# MINIL.net
KiCad netlist of a schematic drawn in EAGLE
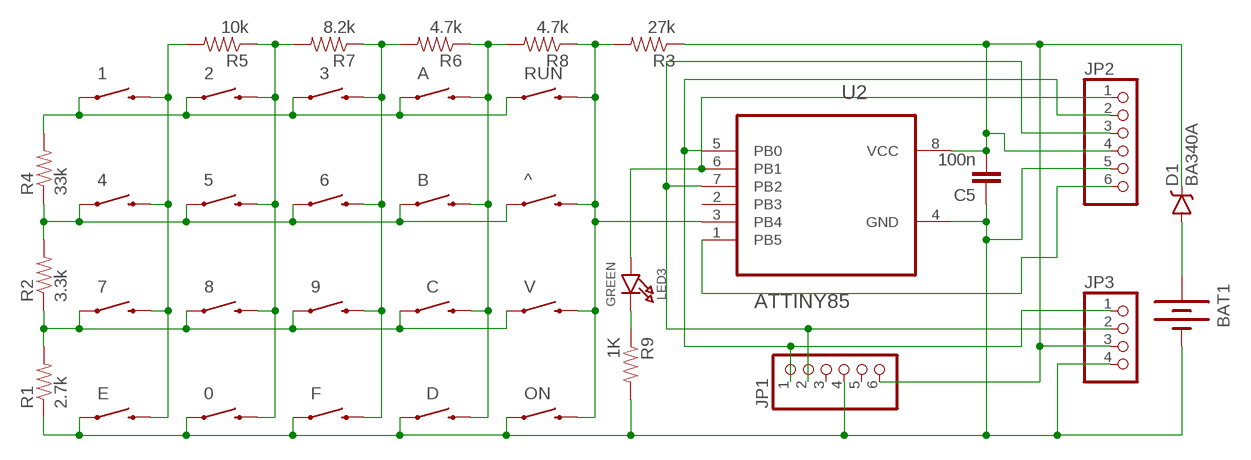
[diagram p0: schematic, sheet 1]

(export (version "E")
  (design (tool "Eeschema 10.0.6"))
  (components
    (comp (ref "0")
      (value "SWITCH-MOMENTARY-2PTH")
      (footprint "eagle-import:TACTILE-PTH")
      (libsource (lib "eagle-import") (part "SWITCH-MOMENTARY-2PTH"))
    )
    (comp (ref "1")
      (value "SWITCH-MOMENTARY-2PTH")
      (footprint "eagle-import:TACTILE-PTH")
      (libsource (lib "eagle-import") (part "SWITCH-MOMENTARY-2PTH"))
    )
    (comp (ref "2")
      (value "SWITCH-MOMENTARY-2PTH")
      (footprint "eagle-import:TACTILE-PTH")
      (libsource (lib "eagle-import") (part "SWITCH-MOMENTARY-2PTH"))
    )
    (comp (ref "3")
      (value "SWITCH-MOMENTARY-2PTH")
      (footprint "eagle-import:TACTILE-PTH")
      (libsource (lib "eagle-import") (part "SWITCH-MOMENTARY-2PTH"))
    )
    (comp (ref "4")
      (value "SWITCH-MOMENTARY-2PTH")
      (footprint "eagle-import:TACTILE-PTH")
      (libsource (lib "eagle-import") (part "SWITCH-MOMENTARY-2PTH"))
    )
    (comp (ref "5")
      (value "SWITCH-MOMENTARY-2PTH")
      (footprint "eagle-import:TACTILE-PTH")
      (libsource (lib "eagle-import") (part "SWITCH-MOMENTARY-2PTH"))
    )
    (comp (ref "6")
      (value "SWITCH-MOMENTARY-2PTH")
      (footprint "eagle-import:TACTILE-PTH")
      (libsource (lib "eagle-import") (part "SWITCH-MOMENTARY-2PTH"))
    )
    (comp (ref "7")
      (value "SWITCH-MOMENTARY-2PTH")
      (footprint "eagle-import:TACTILE-PTH")
      (libsource (lib "eagle-import") (part "SWITCH-MOMENTARY-2PTH"))
    )
    (comp (ref "8")
      (value "SWITCH-MOMENTARY-2PTH")
      (footprint "eagle-import:TACTILE-PTH")
      (libsource (lib "eagle-import") (part "SWITCH-MOMENTARY-2PTH"))
    )
    (comp (ref "9")
      (value "SWITCH-MOMENTARY-2PTH")
      (footprint "eagle-import:TACTILE-PTH")
      (libsource (lib "eagle-import") (part "SWITCH-MOMENTARY-2PTH"))
    )
    (comp (ref "A")
      (value "SWITCH-MOMENTARY-2PTH")
      (footprint "eagle-import:TACTILE-PTH")
      (libsource (lib "eagle-import") (part "SWITCH-MOMENTARY-2PTH"))
    )
    (comp (ref "B")
      (value "SWITCH-MOMENTARY-2PTH")
      (footprint "eagle-import:TACTILE-PTH")
      (libsource (lib "eagle-import") (part "SWITCH-MOMENTARY-2PTH"))
    )
    (comp (ref "BAT1")
      (value "BATTERYAAA-KIT")
      (footprint "eagle-import:BATTERY-AAA-KIT")
      (libsource (lib "eagle-import") (part "BATTERYAAA-KIT"))
    )
    (comp (ref "C")
      (value "SWITCH-MOMENTARY-2PTH")
      (footprint "eagle-import:TACTILE-PTH")
      (libsource (lib "eagle-import") (part "SWITCH-MOMENTARY-2PTH"))
    )
    (comp (ref "C5")
      (value "100n")
      (footprint "eagle-import:0603-CAP")
      (libsource (lib "eagle-import") (part "CAP0603-CAP"))
    )
    (comp (ref "D")
      (value "SWITCH-MOMENTARY-2PTH")
      (footprint "eagle-import:TACTILE-PTH")
      (libsource (lib "eagle-import") (part "SWITCH-MOMENTARY-2PTH"))
    )
    (comp (ref "D1")
      (value "BA340A")
      (footprint "eagle-import:SMA-DIODE")
      (libsource (lib "eagle-import") (part "B340A"))
    )
    (comp (ref "E")
      (value "SWITCH-MOMENTARY-2PTH")
      (footprint "eagle-import:TACTILE-PTH")
      (libsource (lib "eagle-import") (part "SWITCH-MOMENTARY-2PTH"))
    )
    (comp (ref "F")
      (value "SWITCH-MOMENTARY-2PTH")
      (footprint "eagle-import:TACTILE-PTH")
      (libsource (lib "eagle-import") (part "SWITCH-MOMENTARY-2PTH"))
    )
    (comp (ref "JP1")
      (value "HEADER-1X6ROUND")
      (footprint "eagle-import:1X06_ROUND")
      (libsource (lib "eagle-import") (part "HEADER-1X6ROUND"))
    )
    (comp (ref "JP2")
      (value "PINHD-1X6CLEAN")
      (footprint "eagle-import:1X06-CLEAN")
      (libsource (lib "eagle-import") (part "PINHD-1X6CLEAN"))
    )
    (comp (ref "JP3")
      (value "HEADER-1X4ROUND")
      (footprint "eagle-import:1X04_ROUND")
      (libsource (lib "eagle-import") (part "HEADER-1X4ROUND"))
    )
    (comp (ref "LED3")
      (value "GREEN")
      (footprint "eagle-import:CHIPLED_0805_NOOUTLINE")
      (libsource (lib "eagle-import") (part "LED0805_NOOUTLINE"))
    )
    (comp (ref "ON")
      (value "SWITCH-MOMENTARY-2PTH")
      (footprint "eagle-import:TACTILE-PTH")
      (libsource (lib "eagle-import") (part "SWITCH-MOMENTARY-2PTH"))
    )
    (comp (ref "R1")
      (value "2.7k")
      (footprint "eagle-import:0805")
      (libsource (lib "eagle-import") (part "0.3OHM-1/8W-1%(0805)"))
    )
    (comp (ref "R2")
      (value "3.3k")
      (footprint "eagle-import:0805")
      (libsource (lib "eagle-import") (part "0.3OHM-1/8W-1%(0805)"))
    )
    (comp (ref "R3")
      (value "27k")
      (footprint "eagle-import:0805")
      (libsource (lib "eagle-import") (part "0.3OHM-1/8W-1%(0805)"))
    )
    (comp (ref "R4")
      (value "33k")
      (footprint "eagle-import:0805")
      (libsource (lib "eagle-import") (part "0.3OHM-1/8W-1%(0805)"))
    )
    (comp (ref "R5")
      (value "10k")
      (footprint "eagle-import:0805")
      (libsource (lib "eagle-import") (part "0.3OHM-1/8W-1%(0805)"))
    )
    (comp (ref "R6")
      (value "4.7k")
      (footprint "eagle-import:0805")
      (libsource (lib "eagle-import") (part "0.3OHM-1/8W-1%(0805)"))
    )
    (comp (ref "R7")
      (value "8.2k")
      (footprint "eagle-import:0805")
      (libsource (lib "eagle-import") (part "0.3OHM-1/8W-1%(0805)"))
    )
    (comp (ref "R8")
      (value "4.7k")
      (footprint "eagle-import:0805")
      (libsource (lib "eagle-import") (part "0.3OHM-1/8W-1%(0805)"))
    )
    (comp (ref "R9")
      (value "1K")
      (footprint "eagle-import:0805")
      (libsource (lib "eagle-import") (part "0.3OHM-1/8W-1%(0805)"))
    )
    (comp (ref "RUN")
      (value "SWITCH-MOMENTARY-2PTH")
      (footprint "eagle-import:TACTILE-PTH")
      (libsource (lib "eagle-import") (part "SWITCH-MOMENTARY-2PTH"))
    )
    (comp (ref "U2")
      (value "ATTINY85")
      (footprint "eagle-import:SOIC127P798X216-8N")
      (fields (field (name "MPN") "ATTINY85-20SU"))
      (libsource (lib "eagle-import") (part "ATTINY85-20SU"))
    )
    (comp (ref "V")
      (value "SWITCH-MOMENTARY-2PTH")
      (footprint "eagle-import:TACTILE-PTH")
      (libsource (lib "eagle-import") (part "SWITCH-MOMENTARY-2PTH"))
    )
    (comp (ref "^")
      (value "SWITCH-MOMENTARY-2PTH")
      (footprint "eagle-import:TACTILE-PTH")
      (libsource (lib "eagle-import") (part "SWITCH-MOMENTARY-2PTH"))
    )
  )
  (nets
    (net (code "1") (name "Net-(0-2)") (class "Default")
      (node (ref "0") (pin "3") (pinfunction "2_3") (pintype "passive"))
      (node (ref "2") (pin "3") (pinfunction "2_3") (pintype "passive"))
      (node (ref "5") (pin "3") (pinfunction "2_3") (pintype "passive"))
      (node (ref "8") (pin "3") (pinfunction "2_3") (pintype "passive"))
      (node (ref "R5") (pin "1") (pinfunction "1_1") (pintype "passive"))
      (node (ref "R7") (pin "2") (pinfunction "2_2") (pintype "passive"))
    )
    (net (code "2") (name "Net-(1-2)") (class "Default")
      (node (ref "1") (pin "3") (pinfunction "2_3") (pintype "passive"))
      (node (ref "4") (pin "3") (pinfunction "2_3") (pintype "passive"))
      (node (ref "7") (pin "3") (pinfunction "2_3") (pintype "passive"))
      (node (ref "E") (pin "3") (pinfunction "2_3") (pintype "passive"))
      (node (ref "R5") (pin "2") (pinfunction "2_2") (pintype "passive"))
    )
    (net (code "3") (name "Net-(1-Pad1)") (class "Default")
      (node (ref "1") (pin "1") (pinfunction "1_1") (pintype "passive"))
      (node (ref "2") (pin "1") (pinfunction "1_1") (pintype "passive"))
      (node (ref "3") (pin "1") (pinfunction "1_1") (pintype "passive"))
      (node (ref "A") (pin "1") (pinfunction "1_1") (pintype "passive"))
      (node (ref "R4") (pin "2") (pinfunction "2_2") (pintype "passive"))
      (node (ref "RUN") (pin "1") (pinfunction "1_1") (pintype "passive"))
    )
    (net (code "4") (name "Net-(3-2)") (class "Default")
      (node (ref "3") (pin "3") (pinfunction "2_3") (pintype "passive"))
      (node (ref "6") (pin "3") (pinfunction "2_3") (pintype "passive"))
      (node (ref "9") (pin "3") (pinfunction "2_3") (pintype "passive"))
      (node (ref "F") (pin "3") (pinfunction "2_3") (pintype "passive"))
      (node (ref "R6") (pin "2") (pinfunction "2_2") (pintype "passive"))
      (node (ref "R7") (pin "1") (pinfunction "1_1") (pintype "passive"))
    )
    (net (code "5") (name "Net-(4-Pad1)") (class "Default")
      (node (ref "4") (pin "1") (pinfunction "1_1") (pintype "passive"))
      (node (ref "5") (pin "1") (pinfunction "1_1") (pintype "passive"))
      (node (ref "6") (pin "1") (pinfunction "1_1") (pintype "passive"))
      (node (ref "B") (pin "1") (pinfunction "1_1") (pintype "passive"))
      (node (ref "R2") (pin "2") (pinfunction "2_2") (pintype "passive"))
      (node (ref "R4") (pin "1") (pinfunction "1_1") (pintype "passive"))
      (node (ref "^") (pin "1") (pinfunction "1_1") (pintype "passive"))
    )
    (net (code "6") (name "Net-(7-Pad1)") (class "Default")
      (node (ref "7") (pin "1") (pinfunction "1_1") (pintype "passive"))
      (node (ref "8") (pin "1") (pinfunction "1_1") (pintype "passive"))
      (node (ref "9") (pin "1") (pinfunction "1_1") (pintype "passive"))
      (node (ref "C") (pin "1") (pinfunction "1_1") (pintype "passive"))
      (node (ref "R1") (pin "2") (pinfunction "2_2") (pintype "passive"))
      (node (ref "R2") (pin "1") (pinfunction "1_1") (pintype "passive"))
      (node (ref "V") (pin "1") (pinfunction "1_1") (pintype "passive"))
    )
    (net (code "7") (name "Net-(A-2)") (class "Default")
      (node (ref "A") (pin "3") (pinfunction "2_3") (pintype "passive"))
      (node (ref "B") (pin "3") (pinfunction "2_3") (pintype "passive"))
      (node (ref "C") (pin "3") (pinfunction "2_3") (pintype "passive"))
      (node (ref "D") (pin "3") (pinfunction "2_3") (pintype "passive"))
      (node (ref "R6") (pin "1") (pinfunction "1_1") (pintype "passive"))
      (node (ref "R8") (pin "2") (pinfunction "2_2") (pintype "passive"))
    )
    (net (code "8") (name "Net-(BAT1-+)") (class "Default")
      (node (ref "BAT1") (pin "PWR@1") (pinfunction "+_PWR@1") (pintype "power_in"))
      (node (ref "D1") (pin "A") (pinfunction "A_A") (pintype "passive"))
    )
    (net (code "9") (name "Net-(BAT1--)") (class "Default")
      (node (ref "0") (pin "1") (pinfunction "1_1") (pintype "passive"))
      (node (ref "BAT1") (pin "GND@1") (pinfunction "-_GND@1") (pintype "power_in"))
      (node (ref "C5") (pin "1") (pinfunction "1_1") (pintype "passive"))
      (node (ref "D") (pin "1") (pinfunction "1_1") (pintype "passive"))
      (node (ref "E") (pin "1") (pinfunction "1_1") (pintype "passive"))
      (node (ref "F") (pin "1") (pinfunction "1_1") (pintype "passive"))
      (node (ref "JP1") (pin "4") (pinfunction "4_4") (pintype "passive"))
      (node (ref "JP2") (pin "5") (pinfunction "5_5") (pintype "passive"))
      (node (ref "JP3") (pin "4") (pinfunction "4_4") (pintype "passive"))
      (node (ref "ON") (pin "1") (pinfunction "1_1") (pintype "passive"))
      (node (ref "R1") (pin "1") (pinfunction "1_1") (pintype "passive"))
      (node (ref "R9") (pin "2") (pinfunction "2_2") (pintype "passive"))
      (node (ref "U2") (pin "4") (pinfunction "GND_4") (pintype "passive"))
    )
    (net (code "10") (name "Net-(LED3-PadC)") (class "Default")
      (node (ref "LED3") (pin "C") (pinfunction "C_C") (pintype "passive"))
      (node (ref "R9") (pin "1") (pinfunction "1_1") (pintype "passive"))
    )
    (net (code "11") (name "Net-(ON-2)") (class "Default")
      (node (ref "ON") (pin "3") (pinfunction "2_3") (pintype "passive"))
      (node (ref "R3") (pin "2") (pinfunction "2_2") (pintype "passive"))
      (node (ref "R8") (pin "1") (pinfunction "1_1") (pintype "passive"))
      (node (ref "RUN") (pin "3") (pinfunction "2_3") (pintype "passive"))
      (node (ref "U2") (pin "3") (pinfunction "PB4_3") (pintype "bidirectional"))
      (node (ref "V") (pin "3") (pinfunction "2_3") (pintype "passive"))
      (node (ref "^") (pin "3") (pinfunction "2_3") (pintype "passive"))
    )
    (net (code "12") (name "Net-(U2-PB0)") (class "Default")
      (node (ref "JP1") (pin "1") (pinfunction "1_1") (pintype "passive"))
      (node (ref "JP2") (pin "2") (pinfunction "2_2") (pintype "passive"))
      (node (ref "JP3") (pin "1") (pinfunction "1_1") (pintype "passive"))
      (node (ref "U2") (pin "5") (pinfunction "PB0_5") (pintype "bidirectional"))
    )
    (net (code "13") (name "Net-(U2-PB1)") (class "Default")
      (node (ref "JP2") (pin "1") (pinfunction "1_1") (pintype "passive"))
      (node (ref "LED3") (pin "A") (pinfunction "A_A") (pintype "passive"))
      (node (ref "U2") (pin "6") (pinfunction "PB1_6") (pintype "bidirectional"))
    )
    (net (code "14") (name "Net-(U2-PB2)") (class "Default")
      (node (ref "JP1") (pin "2") (pinfunction "2_2") (pintype "passive"))
      (node (ref "JP2") (pin "3") (pinfunction "3_3") (pintype "passive"))
      (node (ref "JP3") (pin "2") (pinfunction "2_2") (pintype "passive"))
      (node (ref "U2") (pin "7") (pinfunction "PB2_7") (pintype "bidirectional"))
    )
    (net (code "15") (name "Net-(U2-PB5)") (class "Default")
      (node (ref "JP2") (pin "6") (pinfunction "6_6") (pintype "passive"))
      (node (ref "U2") (pin "1") (pinfunction "PB5_1") (pintype "bidirectional"))
    )
    (net (code "16") (name "Net-(U2-VCC)") (class "Default")
      (node (ref "C5") (pin "2") (pinfunction "2_2") (pintype "passive"))
      (node (ref "D1") (pin "C") (pinfunction "C_C") (pintype "passive"))
      (node (ref "JP1") (pin "6") (pinfunction "6_6") (pintype "passive"))
      (node (ref "JP2") (pin "4") (pinfunction "4_4") (pintype "passive"))
      (node (ref "JP3") (pin "3") (pinfunction "3_3") (pintype "passive"))
      (node (ref "R3") (pin "1") (pinfunction "1_1") (pintype "passive"))
      (node (ref "U2") (pin "8") (pinfunction "VCC_8") (pintype "power_in"))
    )
    (net (code "17") (name "unconnected-(JP1-Pad3)") (class "Default")
      (node (ref "JP1") (pin "3") (pinfunction "3_3") (pintype "passive"))
    )
    (net (code "18") (name "unconnected-(JP1-Pad5)") (class "Default")
      (node (ref "JP1") (pin "5") (pinfunction "5_5") (pintype "passive"))
    )
    (net (code "19") (name "unconnected-(U2-PB3-Pad2)") (class "Default")
      (node (ref "U2") (pin "2") (pinfunction "PB3_2") (pintype "bidirectional"))
    )
  )
)
